# led_board.net
KiCad netlist of a schematic drawn in Altium Designer
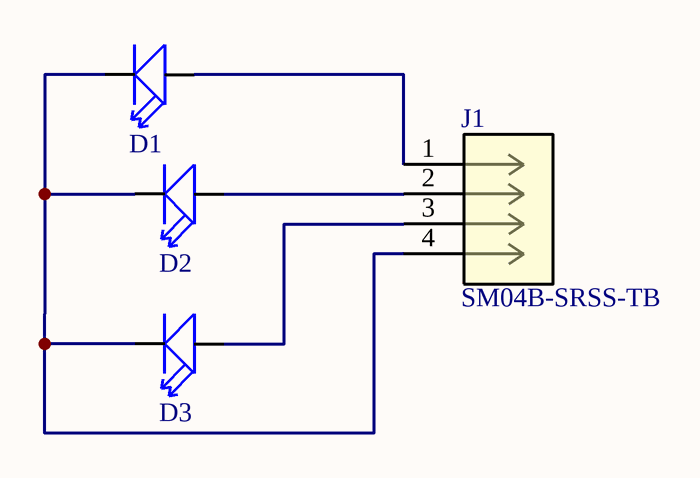
[diagram p0: led_board.SchDoc]

(export (version "E")
  (design (tool "Eeschema 10.0.6"))
  (components
    (comp (ref "D1")
      (value "LED")
      (footprint "LEDM1608X80")
      (description "Single Color LED, Ultra Bright Orange, Water Clear, 1.1mm")
      (fields
        (field (name "MANUFACTURER") "Vishay Lite-On")
        (field (name "MANUFACTURER PART NUMBER") "LTST-C190KFKT")
      )
      (libsource (lib "Passive") (part "LTST-C190KFKT"))
    )
    (comp (ref "D2")
      (value "LED")
      (footprint "LEDM1608X80")
      (description "Single Color LED, Ultra Bright Orange, Water Clear, 1.1mm")
      (fields
        (field (name "MANUFACTURER") "Vishay Lite-On")
        (field (name "MANUFACTURER PART NUMBER") "LTST-C190KFKT")
      )
      (libsource (lib "Passive") (part "LTST-C190KFKT"))
    )
    (comp (ref "D3")
      (value "LED")
      (footprint "LEDM1608X80")
      (description "Single Color LED, Ultra Bright Orange, Water Clear, 1.1mm")
      (fields
        (field (name "MANUFACTURER") "Vishay Lite-On")
        (field (name "MANUFACTURER PART NUMBER") "LTST-C190KFKT")
      )
      (libsource (lib "Passive") (part "LTST-C190KFKT"))
    )
    (comp (ref "J1")
      (value "SM04B-SRSS-TB")
      (footprint "CONN_SM04B-SRSS-TB_JST")
      (description "No Description Available")
      (fields (field (name "COPYRIGHT") "Copyright (C) 2025 Ultra Librarian. All rights reserved."))
      (libsource (lib "Connectors") (part "SM04B-SRSS-TB"))
    )
  )
  (nets
    (net (code "1") (name "Net-(D1-PadA)") (class "Default")
      (node (ref "D1") (pin "A") (pinfunction "A_A") (pintype "passive"))
      (node (ref "J1") (pin "1") (pinfunction "1_1") (pintype "passive"))
    )
    (net (code "2") (name "Net-(D1-PadC)") (class "Default")
      (node (ref "D1") (pin "C") (pinfunction "C_C") (pintype "passive"))
      (node (ref "D2") (pin "C") (pinfunction "C_C") (pintype "passive"))
      (node (ref "D3") (pin "C") (pinfunction "C_C") (pintype "passive"))
      (node (ref "J1") (pin "4") (pinfunction "4_4") (pintype "passive"))
    )
    (net (code "3") (name "Net-(D2-PadA)") (class "Default")
      (node (ref "D2") (pin "A") (pinfunction "A_A") (pintype "passive"))
      (node (ref "J1") (pin "2") (pinfunction "2_2") (pintype "passive"))
    )
    (net (code "4") (name "Net-(D3-PadA)") (class "Default")
      (node (ref "D3") (pin "A") (pinfunction "A_A") (pintype "passive"))
      (node (ref "J1") (pin "3") (pinfunction "3_3") (pintype "passive"))
    )
  )
)
